# receiver.net
KiCad netlist of a schematic drawn in EAGLE
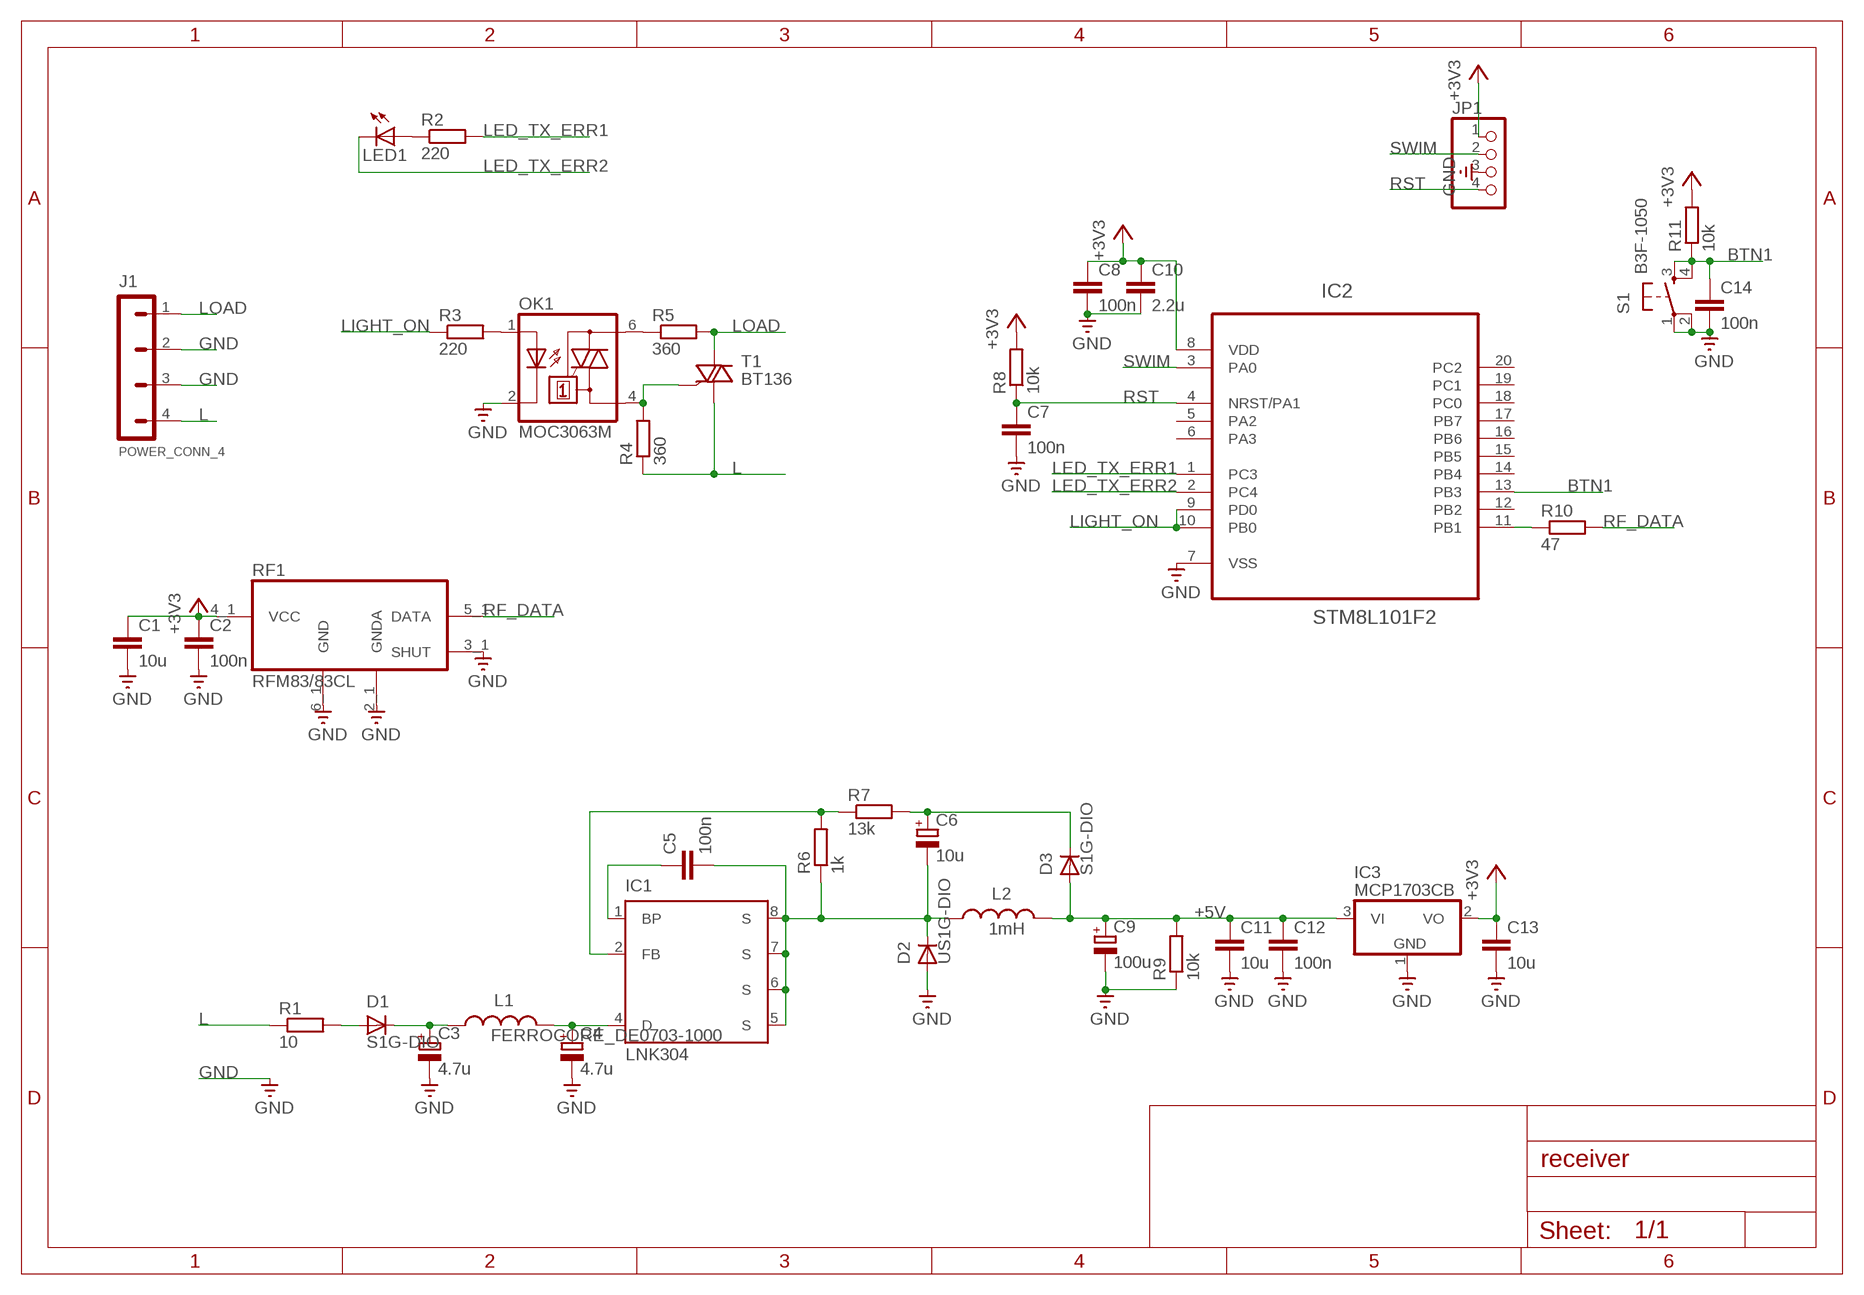
[diagram p0: schematic, sheet 1]

(export (version "E")
  (design (tool "Eeschema 10.0.6"))
  (components
    (comp (ref "C1")
      (value "10u")
      (footprint "eagle-import:C1206")
      (libsource (lib "eagle-import") (part "C-EUC1206"))
    )
    (comp (ref "C2")
      (value "100n")
      (footprint "eagle-import:C0603K")
      (libsource (lib "eagle-import") (part "C-EUC0603K"))
    )
    (comp (ref "C3")
      (value "4.7u")
      (footprint "eagle-import:CAP_10X12.5_AIR")
      (libsource (lib "eagle-import") (part "C-POL-EUCAP_10X12.5_AIR"))
    )
    (comp (ref "C4")
      (value "4.7u")
      (footprint "eagle-import:E5-10,5")
      (libsource (lib "eagle-import") (part "C-POL-EUE5-10,5"))
    )
    (comp (ref "C5")
      (value "100n")
      (footprint "eagle-import:C0603K")
      (libsource (lib "eagle-import") (part "C-EUC0603K"))
    )
    (comp (ref "C6")
      (value "10u")
      (footprint "eagle-import:PANASONIC_C_LARGER_PADS")
      (libsource (lib "eagle-import") (part "C_POL_PANASONIC_C_LARGER_PADS"))
    )
    (comp (ref "C7")
      (value "100n")
      (footprint "eagle-import:C0603K")
      (libsource (lib "eagle-import") (part "C-EUC0603K"))
    )
    (comp (ref "C8")
      (value "100n")
      (footprint "eagle-import:C0603K")
      (libsource (lib "eagle-import") (part "C-EUC0603K"))
    )
    (comp (ref "C9")
      (value "100u")
      (footprint "eagle-import:PANASONIC_D_LARGER_PADS")
      (libsource (lib "eagle-import") (part "C-POL_PANASONC_D_LARGER_PADS"))
    )
    (comp (ref "C10")
      (value "2.2u")
      (footprint "eagle-import:C1206")
      (libsource (lib "eagle-import") (part "C-EUC1206"))
    )
    (comp (ref "C11")
      (value "10u")
      (footprint "eagle-import:C1206")
      (libsource (lib "eagle-import") (part "C-EUC1206"))
    )
    (comp (ref "C12")
      (value "100n")
      (footprint "eagle-import:C0603K")
      (libsource (lib "eagle-import") (part "C-EUC0603K"))
    )
    (comp (ref "C13")
      (value "10u")
      (footprint "eagle-import:C1206")
      (libsource (lib "eagle-import") (part "C-EUC1206"))
    )
    (comp (ref "C14")
      (value "100n")
      (footprint "eagle-import:C0603K")
      (libsource (lib "eagle-import") (part "C-EUC0603K"))
    )
    (comp (ref "D1")
      (value "S1G-DIO")
      (footprint "eagle-import:DO214-AC")
      (libsource (lib "eagle-import") (part "S1G-DIO"))
    )
    (comp (ref "D2")
      (value "US1G-DIO")
      (footprint "eagle-import:DO214-AC")
      (libsource (lib "eagle-import") (part "US1G-DIO"))
    )
    (comp (ref "D3")
      (value "S1G-DIO")
      (footprint "eagle-import:DO214-AC")
      (libsource (lib "eagle-import") (part "S1G-DIO"))
    )
    (comp (ref "IC1")
      (value "LNK304")
      (footprint "eagle-import:SO8_NO_PIN3")
      (libsource (lib "eagle-import") (part "LNK304"))
    )
    (comp (ref "IC2")
      (value "STM8L101F2")
      (footprint "eagle-import:TSSOP20")
      (libsource (lib "eagle-import") (part "STM8L101F2"))
    )
    (comp (ref "IC3")
      (value "MCP1703CB")
      (footprint "eagle-import:SOT23")
      (libsource (lib "eagle-import") (part "MCP1703CB"))
    )
    (comp (ref "J1")
      (value "POWER_CONN_4")
      (footprint "eagle-import:TERMINAL_BLOCK_4")
      (libsource (lib "eagle-import") (part "POWER_CONN_4"))
    )
    (comp (ref "JP1")
      (value "CON_1X4PIN_2.54MM_SMD")
      (footprint "eagle-import:CON_1X4_2.54_SMD")
      (libsource (lib "eagle-import") (part "CON_1X4PIN_2.54MM_SMD"))
    )
    (comp (ref "L1")
      (value "FERROCORE_DE0703-1000")
      (footprint "eagle-import:DE0703")
      (libsource (lib "eagle-import") (part "FERROCORE_DE0703-1000"))
    )
    (comp (ref "L2")
      (value "1mH")
      (footprint "eagle-import:DE0703")
      (libsource (lib "eagle-import") (part "FERROCORE_DE0703-1000"))
    )
    (comp (ref "LED1")
      (value "LED3MM")
      (footprint "eagle-import:LED3MM")
      (libsource (lib "eagle-import") (part "LED3MM"))
    )
    (comp (ref "OK1")
      (value "MOC3063M")
      (footprint "eagle-import:DIL06")
      (fields (field (name "MF") "FAIRCHILD SEMICONDUCTOR") (field (name "MPN") "MOC3023-M"))
      (libsource (lib "eagle-import") (part "MOC30M23"))
    )
    (comp (ref "R1")
      (value "10")
      (footprint "eagle-import:R2512_LARGER_PADS")
      (libsource (lib "eagle-import") (part "R_R2512_LARGER_PADS"))
    )
    (comp (ref "R2")
      (value "220")
      (footprint "eagle-import:R0603")
      (libsource (lib "eagle-import") (part "R-EU_R0603"))
    )
    (comp (ref "R3")
      (value "220")
      (footprint "eagle-import:R0603")
      (libsource (lib "eagle-import") (part "R-EU_R0603"))
    )
    (comp (ref "R4")
      (value "360")
      (footprint "eagle-import:R0603")
      (libsource (lib "eagle-import") (part "R-EU_R0603"))
    )
    (comp (ref "R5")
      (value "360")
      (footprint "eagle-import:R0603")
      (libsource (lib "eagle-import") (part "R-EU_R0603"))
    )
    (comp (ref "R6")
      (value "1k")
      (footprint "eagle-import:R0603")
      (libsource (lib "eagle-import") (part "R-EU_R0603"))
    )
    (comp (ref "R7")
      (value "13k")
      (footprint "eagle-import:R0603")
      (libsource (lib "eagle-import") (part "R-EU_R0603"))
    )
    (comp (ref "R8")
      (value "10k")
      (footprint "eagle-import:R0603")
      (libsource (lib "eagle-import") (part "R-EU_R0603"))
    )
    (comp (ref "R9")
      (value "10k")
      (footprint "eagle-import:R0603")
      (libsource (lib "eagle-import") (part "R-EU_R0603"))
    )
    (comp (ref "R10")
      (value "47")
      (footprint "eagle-import:R0603")
      (libsource (lib "eagle-import") (part "R-EU_R0603"))
    )
    (comp (ref "R11")
      (value "10k")
      (footprint "eagle-import:R0603")
      (libsource (lib "eagle-import") (part "R-EU_R0603"))
    )
    (comp (ref "RF1")
      (value "RFM83/83CL")
      (footprint "eagle-import:RFM83C_83CL_CONN")
      (libsource (lib "eagle-import") (part "RFM83/83CL"))
    )
    (comp (ref "S1")
      (value "B3F-1050")
      (footprint "eagle-import:DTS-6")
      (libsource (lib "eagle-import") (part "DTS-6"))
    )
    (comp (ref "T1")
      (value "BT136")
      (footprint "eagle-import:TO220AB")
      (libsource (lib "eagle-import") (part "BT136"))
    )
  )
  (nets
    (net (code "1") (name "+3V3") (class "Default")
      (node (ref "C1") (pin "1") (pinfunction "1_1") (pintype "passive"))
      (node (ref "C10") (pin "1") (pinfunction "1_1") (pintype "passive"))
      (node (ref "C13") (pin "1") (pinfunction "1_1") (pintype "passive"))
      (node (ref "C2") (pin "1") (pinfunction "1_1") (pintype "passive"))
      (node (ref "C8") (pin "1") (pinfunction "1_1") (pintype "passive"))
      (node (ref "IC2") (pin "8") (pinfunction "VDD_8") (pintype "power_in"))
      (node (ref "IC3") (pin "2") (pinfunction "VO_2") (pintype "passive"))
      (node (ref "JP1") (pin "1") (pinfunction "1_1") (pintype "passive"))
      (node (ref "R11") (pin "2") (pinfunction "2_2") (pintype "passive"))
      (node (ref "R8") (pin "2") (pinfunction "2_2") (pintype "passive"))
      (node (ref "RF1") (pin "4_1") (pinfunction "VCC_4_1") (pintype "power_in"))
    )
    (net (code "2") (name "/+5V") (class "Default")
      (node (ref "C11") (pin "1") (pinfunction "1_1") (pintype "passive"))
      (node (ref "C12") (pin "1") (pinfunction "1_1") (pintype "passive"))
      (node (ref "C9") (pin "+") (pinfunction "+_+") (pintype "passive"))
      (node (ref "D3") (pin "A") (pinfunction "A_A") (pintype "passive"))
      (node (ref "IC3") (pin "3") (pinfunction "VI_3") (pintype "input"))
      (node (ref "L2") (pin "P$2") (pinfunction "2_P$2") (pintype "passive"))
      (node (ref "R9") (pin "2") (pinfunction "2_2") (pintype "passive"))
    )
    (net (code "3") (name "/BTN1") (class "Default")
      (node (ref "C14") (pin "1") (pinfunction "1_1") (pintype "passive"))
      (node (ref "IC2") (pin "13") (pinfunction "PB3_13") (pintype "bidirectional"))
      (node (ref "R11") (pin "1") (pinfunction "1_1") (pintype "passive"))
      (node (ref "S1") (pin "3") (pinfunction "3_3") (pintype "passive"))
      (node (ref "S1") (pin "4") (pinfunction "4_4") (pintype "passive"))
    )
    (net (code "4") (name "/L") (class "Default")
      (node (ref "J1") (pin "4") (pinfunction "P$4_4") (pintype "bidirectional"))
      (node (ref "R1") (pin "1") (pinfunction "1_1") (pintype "passive"))
      (node (ref "R4") (pin "1") (pinfunction "1_1") (pintype "passive"))
      (node (ref "T1") (pin "1") (pinfunction "A1_1") (pintype "passive"))
    )
    (net (code "5") (name "/LED_TX_ERR1") (class "Default")
      (node (ref "IC2") (pin "1") (pinfunction "PC3_1") (pintype "bidirectional"))
      (node (ref "R2") (pin "2") (pinfunction "2_2") (pintype "passive"))
    )
    (net (code "6") (name "/LED_TX_ERR2") (class "Default")
      (node (ref "IC2") (pin "2") (pinfunction "PC4_2") (pintype "bidirectional"))
      (node (ref "LED1") (pin "K") (pinfunction "C_K") (pintype "passive"))
    )
    (net (code "7") (name "/LIGHT_ON") (class "Default")
      (node (ref "IC2") (pin "10") (pinfunction "PB0_10") (pintype "bidirectional"))
      (node (ref "IC2") (pin "9") (pinfunction "PD0_9") (pintype "bidirectional"))
      (node (ref "R3") (pin "1") (pinfunction "1_1") (pintype "passive"))
    )
    (net (code "8") (name "/LOAD") (class "Default")
      (node (ref "J1") (pin "1") (pinfunction "P$1_1") (pintype "bidirectional"))
      (node (ref "R5") (pin "2") (pinfunction "2_2") (pintype "passive"))
      (node (ref "T1") (pin "2") (pinfunction "A2_2") (pintype "passive"))
    )
    (net (code "9") (name "/RF_DATA") (class "Default")
      (node (ref "R10") (pin "2") (pinfunction "2_2") (pintype "passive"))
      (node (ref "RF1") (pin "5_1") (pinfunction "DATA_5_1") (pintype "output"))
    )
    (net (code "10") (name "/RST") (class "Default")
      (node (ref "C7") (pin "1") (pinfunction "1_1") (pintype "passive"))
      (node (ref "IC2") (pin "4") (pinfunction "NRST/PA1_4") (pintype "bidirectional"))
      (node (ref "JP1") (pin "4") (pinfunction "4_4") (pintype "passive"))
      (node (ref "R8") (pin "1") (pinfunction "1_1") (pintype "passive"))
    )
    (net (code "11") (name "/SWIM") (class "Default")
      (node (ref "IC2") (pin "3") (pinfunction "PA0_3") (pintype "power_in"))
      (node (ref "JP1") (pin "2") (pinfunction "2_2") (pintype "passive"))
    )
    (net (code "12") (name "GND") (class "Default")
      (node (ref "C1") (pin "2") (pinfunction "2_2") (pintype "passive"))
      (node (ref "C10") (pin "2") (pinfunction "2_2") (pintype "passive"))
      (node (ref "C11") (pin "2") (pinfunction "2_2") (pintype "passive"))
      (node (ref "C12") (pin "2") (pinfunction "2_2") (pintype "passive"))
      (node (ref "C13") (pin "2") (pinfunction "2_2") (pintype "passive"))
      (node (ref "C14") (pin "2") (pinfunction "2_2") (pintype "passive"))
      (node (ref "C2") (pin "2") (pinfunction "2_2") (pintype "passive"))
      (node (ref "C3") (pin "-") (pinfunction "-_-") (pintype "passive"))
      (node (ref "C4") (pin "-") (pinfunction "-_-") (pintype "passive"))
      (node (ref "C7") (pin "2") (pinfunction "2_2") (pintype "passive"))
      (node (ref "C8") (pin "2") (pinfunction "2_2") (pintype "passive"))
      (node (ref "C9") (pin "-") (pinfunction "-_-") (pintype "passive"))
      (node (ref "D2") (pin "A") (pinfunction "A_A") (pintype "passive"))
      (node (ref "IC2") (pin "7") (pinfunction "VSS_7") (pintype "power_in"))
      (node (ref "IC3") (pin "1") (pinfunction "GND_1") (pintype "passive"))
      (node (ref "J1") (pin "2") (pinfunction "P$2_2") (pintype "bidirectional"))
      (node (ref "J1") (pin "3") (pinfunction "P$3_3") (pintype "bidirectional"))
      (node (ref "JP1") (pin "3") (pinfunction "3_3") (pintype "passive"))
      (node (ref "OK1") (pin "2") (pinfunction "C_2") (pintype "passive"))
      (node (ref "R9") (pin "1") (pinfunction "1_1") (pintype "passive"))
      (node (ref "RF1") (pin "2_1") (pinfunction "GNDA_2_1") (pintype "power_in"))
      (node (ref "RF1") (pin "3_1") (pinfunction "SHUT_3_1") (pintype "input"))
      (node (ref "RF1") (pin "6_1") (pinfunction "GND_6_1") (pintype "power_in"))
      (node (ref "S1") (pin "1") (pinfunction "1_1") (pintype "passive"))
      (node (ref "S1") (pin "2") (pinfunction "2_2") (pintype "passive"))
    )
    (net (code "13") (name "Net-(C6-Pad+)") (class "Default")
      (node (ref "C6") (pin "+") (pinfunction "+_+") (pintype "passive"))
      (node (ref "D3") (pin "C") (pinfunction "C_C") (pintype "passive"))
      (node (ref "R7") (pin "2") (pinfunction "2_2") (pintype "passive"))
    )
    (net (code "14") (name "Net-(D1-PadA)") (class "Default")
      (node (ref "D1") (pin "A") (pinfunction "A_A") (pintype "passive"))
      (node (ref "R1") (pin "2") (pinfunction "2_2") (pintype "passive"))
    )
    (net (code "15") (name "Net-(IC1-BP)") (class "Default")
      (node (ref "C5") (pin "1") (pinfunction "1_1") (pintype "passive"))
      (node (ref "IC1") (pin "1") (pinfunction "BP_1") (pintype "power_in"))
    )
    (net (code "16") (name "Net-(IC1-D)") (class "Default")
      (node (ref "C4") (pin "+") (pinfunction "+_+") (pintype "passive"))
      (node (ref "IC1") (pin "4") (pinfunction "D_4") (pintype "power_in"))
      (node (ref "L1") (pin "P$2") (pinfunction "2_P$2") (pintype "passive"))
    )
    (net (code "17") (name "Net-(IC1-FB)") (class "Default")
      (node (ref "IC1") (pin "2") (pinfunction "FB_2") (pintype "input"))
      (node (ref "R6") (pin "2") (pinfunction "2_2") (pintype "passive"))
      (node (ref "R7") (pin "1") (pinfunction "1_1") (pintype "passive"))
    )
    (net (code "18") (name "Net-(IC2-PB1)") (class "Default")
      (node (ref "IC2") (pin "11") (pinfunction "PB1_11") (pintype "bidirectional"))
      (node (ref "R10") (pin "1") (pinfunction "1_1") (pintype "passive"))
    )
    (net (code "19") (name "Net-(L1-1)") (class "Default")
      (node (ref "C3") (pin "+") (pinfunction "+_+") (pintype "passive"))
      (node (ref "D1") (pin "C") (pinfunction "C_C") (pintype "passive"))
      (node (ref "L1") (pin "P$1") (pinfunction "1_P$1") (pintype "passive"))
    )
    (net (code "20") (name "Net-(L2-1)") (class "Default")
      (node (ref "C5") (pin "2") (pinfunction "2_2") (pintype "passive"))
      (node (ref "C6") (pin "-") (pinfunction "-_-") (pintype "passive"))
      (node (ref "D2") (pin "C") (pinfunction "C_C") (pintype "passive"))
      (node (ref "IC1") (pin "5") (pinfunction "S_5") (pintype "power_in"))
      (node (ref "IC1") (pin "6") (pinfunction "S_6") (pintype "power_in"))
      (node (ref "IC1") (pin "7") (pinfunction "S_7") (pintype "power_in"))
      (node (ref "IC1") (pin "8") (pinfunction "S_8") (pintype "power_in"))
      (node (ref "L2") (pin "P$1") (pinfunction "1_P$1") (pintype "passive"))
      (node (ref "R6") (pin "1") (pinfunction "1_1") (pintype "passive"))
    )
    (net (code "21") (name "Net-(LED1-PadA)") (class "Default")
      (node (ref "LED1") (pin "A") (pinfunction "A_A") (pintype "passive"))
      (node (ref "R2") (pin "1") (pinfunction "1_1") (pintype "passive"))
    )
    (net (code "22") (name "Net-(OK1-A)") (class "Default")
      (node (ref "OK1") (pin "1") (pinfunction "A_1") (pintype "passive"))
      (node (ref "R3") (pin "2") (pinfunction "2_2") (pintype "passive"))
    )
    (net (code "23") (name "Net-(OK1-A1)") (class "Default")
      (node (ref "OK1") (pin "4") (pinfunction "A1_4") (pintype "passive"))
      (node (ref "R4") (pin "2") (pinfunction "2_2") (pintype "passive"))
      (node (ref "T1") (pin "3") (pinfunction "G_3") (pintype "passive"))
    )
    (net (code "24") (name "Net-(OK1-A2)") (class "Default")
      (node (ref "OK1") (pin "6") (pinfunction "A2_6") (pintype "passive"))
      (node (ref "R5") (pin "1") (pinfunction "1_1") (pintype "passive"))
    )
    (net (code "25") (name "unconnected-(IC2-PA2-Pad5)") (class "Default")
      (node (ref "IC2") (pin "5") (pinfunction "PA2_5") (pintype "bidirectional"))
    )
    (net (code "26") (name "unconnected-(IC2-PA3-Pad6)") (class "Default")
      (node (ref "IC2") (pin "6") (pinfunction "PA3_6") (pintype "bidirectional"))
    )
    (net (code "27") (name "unconnected-(IC2-PB2-Pad12)") (class "Default")
      (node (ref "IC2") (pin "12") (pinfunction "PB2_12") (pintype "bidirectional"))
    )
    (net (code "28") (name "unconnected-(IC2-PB4-Pad14)") (class "Default")
      (node (ref "IC2") (pin "14") (pinfunction "PB4_14") (pintype "bidirectional"))
    )
    (net (code "29") (name "unconnected-(IC2-PB5-Pad15)") (class "Default")
      (node (ref "IC2") (pin "15") (pinfunction "PB5_15") (pintype "bidirectional"))
    )
    (net (code "30") (name "unconnected-(IC2-PB6-Pad16)") (class "Default")
      (node (ref "IC2") (pin "16") (pinfunction "PB6_16") (pintype "bidirectional"))
    )
    (net (code "31") (name "unconnected-(IC2-PB7-Pad17)") (class "Default")
      (node (ref "IC2") (pin "17") (pinfunction "PB7_17") (pintype "bidirectional"))
    )
    (net (code "32") (name "unconnected-(IC2-PC0-Pad18)") (class "Default")
      (node (ref "IC2") (pin "18") (pinfunction "PC0_18") (pintype "bidirectional"))
    )
    (net (code "33") (name "unconnected-(IC2-PC1-Pad19)") (class "Default")
      (node (ref "IC2") (pin "19") (pinfunction "PC1_19") (pintype "bidirectional"))
    )
    (net (code "34") (name "unconnected-(IC2-PC2-Pad20)") (class "Default")
      (node (ref "IC2") (pin "20") (pinfunction "PC2_20") (pintype "bidirectional"))
    )
  )
)
